# Power.net
KiCad netlist of a schematic drawn in Altium Designer
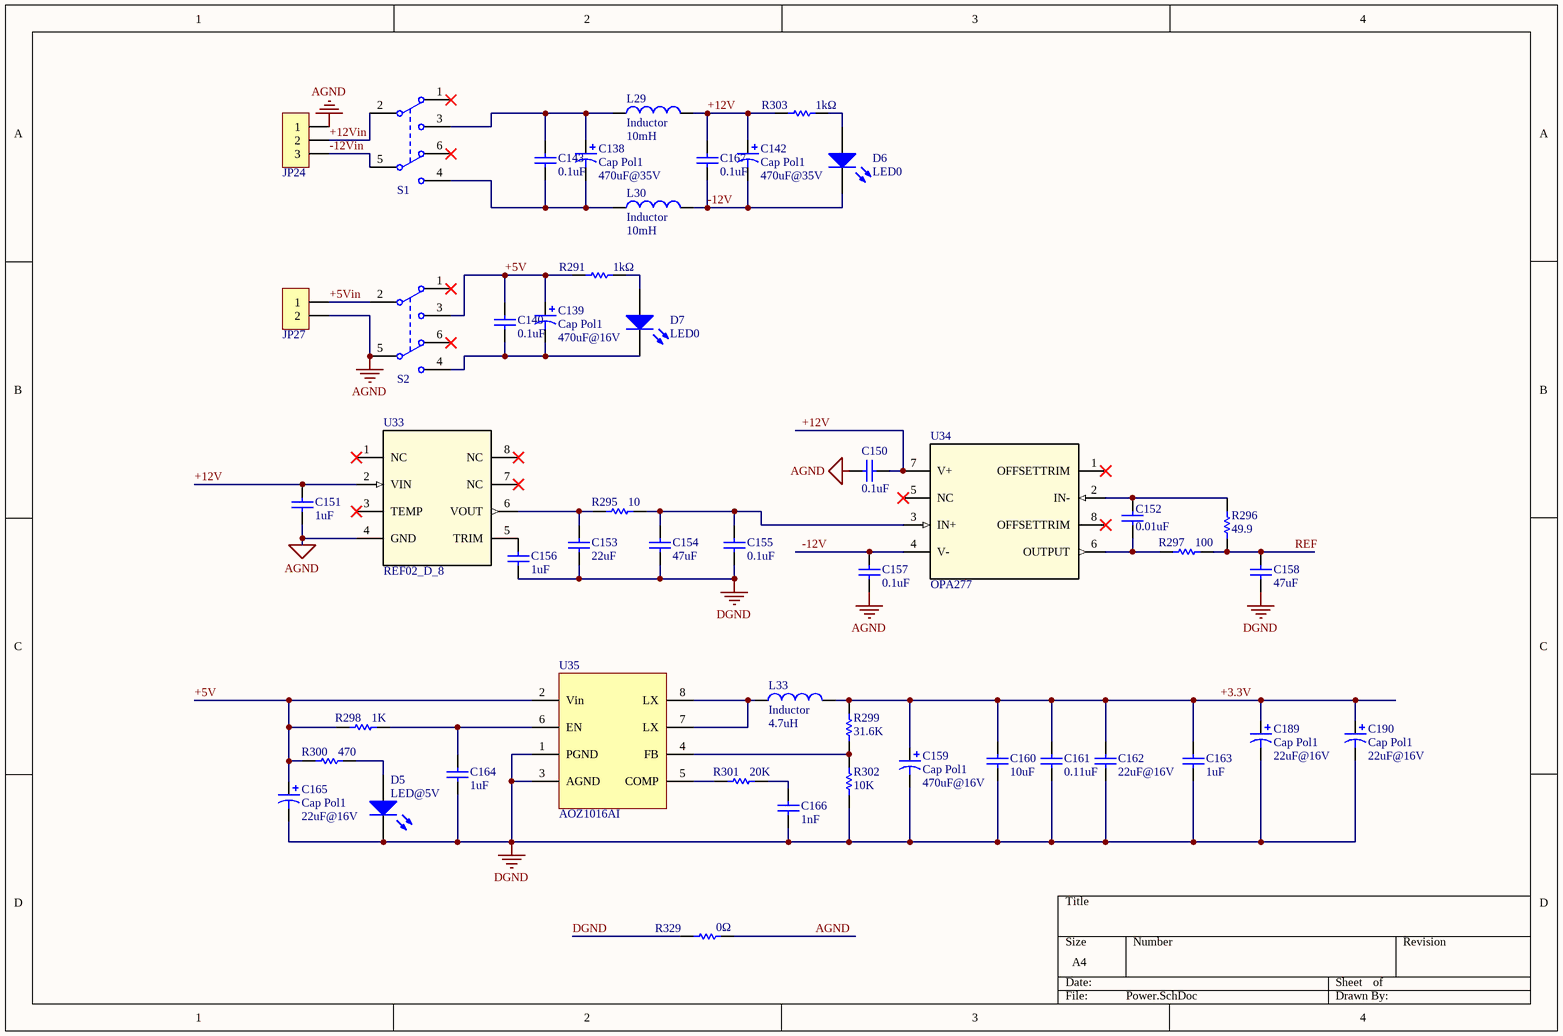
[diagram p0: Power.SchDoc]

(export (version "E")
  (design (tool "Eeschema 10.0.6"))
  (components
    (comp (ref "C138")
      (value "Cap Pol1")
      (footprint "RB7.6-15")
      (description "Polarized Capacitor (Radial)")
      (fields (field (name "ALTIUM_VALUE") "470uF@35V") (field (name "PUBLISHER") "Altium Limited"))
      (libsource (lib "Miscellaneous Devices") (part "Cap Pol1"))
    )
    (comp (ref "C139")
      (value "Cap Pol1")
      (footprint "RB7.6-15")
      (description "Polarized Capacitor (Radial)")
      (fields (field (name "ALTIUM_VALUE") "470uF@16V") (field (name "PUBLISHER") "Altium Limited"))
      (libsource (lib "Miscellaneous Devices") (part "Cap Pol1"))
    )
    (comp (ref "C140")
      (value "0.1uF")
      (footprint "1608[0603]")
      (description "Capacitor")
      (fields (field (name "Comment") "Cap") (field (name "PUBLISHER") "Altium Limited"))
      (libsource (lib "Miscellaneous Devices") (part "Cap"))
    )
    (comp (ref "C142")
      (value "Cap Pol1")
      (footprint "RB7.6-15")
      (description "Polarized Capacitor (Radial)")
      (fields (field (name "ALTIUM_VALUE") "470uF@35V") (field (name "PUBLISHER") "Altium Limited"))
      (libsource (lib "Miscellaneous Devices") (part "Cap Pol1"))
    )
    (comp (ref "C143")
      (value "0.1uF")
      (footprint "1608[0603]")
      (description "Capacitor")
      (fields (field (name "Comment") "Cap") (field (name "PUBLISHER") "Altium Limited"))
      (libsource (lib "Miscellaneous Devices") (part "Cap"))
    )
    (comp (ref "C150")
      (value "0.1uF")
      (footprint "1608[0603]")
      (description "Capacitor")
      (fields (field (name "Comment") "Cap") (field (name "PUBLISHER") "Altium Limited"))
      (libsource (lib "Miscellaneous Devices") (part "Cap"))
    )
    (comp (ref "C151")
      (value "1uF")
      (footprint "1608[0603]")
      (description "Capacitor")
      (fields (field (name "Comment") "Cap") (field (name "PUBLISHER") "Altium Limited"))
      (libsource (lib "Miscellaneous Devices") (part "Cap"))
    )
    (comp (ref "C152")
      (value "0.01uF")
      (footprint "1608[0603]")
      (description "Capacitor")
      (fields (field (name "Comment") "Cap") (field (name "PUBLISHER") "Altium Limited"))
      (libsource (lib "Miscellaneous Devices") (part "Cap"))
    )
    (comp (ref "C153")
      (value "22uF")
      (footprint "C0805")
      (description "Capacitor")
      (fields (field (name "Comment") "Cap") (field (name "PUBLISHER") "Altium Limited"))
      (libsource (lib "Miscellaneous Devices") (part "Cap"))
    )
    (comp (ref "C154")
      (value "47uF")
      (footprint "C1206")
      (description "Capacitor")
      (fields (field (name "Comment") "Cap") (field (name "PUBLISHER") "Altium Limited"))
      (libsource (lib "Miscellaneous Devices") (part "Cap"))
    )
    (comp (ref "C155")
      (value "0.1uF")
      (footprint "1608[0603]")
      (description "Capacitor")
      (fields (field (name "Comment") "Cap") (field (name "PUBLISHER") "Altium Limited"))
      (libsource (lib "Miscellaneous Devices") (part "Cap"))
    )
    (comp (ref "C156")
      (value "1uF")
      (footprint "1608[0603]")
      (description "Capacitor")
      (fields (field (name "Comment") "Cap") (field (name "PUBLISHER") "Altium Limited"))
      (libsource (lib "Miscellaneous Devices") (part "Cap"))
    )
    (comp (ref "C157")
      (value "0.1uF")
      (footprint "1608[0603]")
      (description "Capacitor")
      (fields (field (name "Comment") "Cap") (field (name "PUBLISHER") "Altium Limited"))
      (libsource (lib "Miscellaneous Devices") (part "Cap"))
    )
    (comp (ref "C158")
      (value "47uF")
      (footprint "C1206")
      (description "Capacitor")
      (fields (field (name "Comment") "Cap") (field (name "PUBLISHER") "Altium Limited"))
      (libsource (lib "Miscellaneous Devices") (part "Cap"))
    )
    (comp (ref "C159")
      (value "Cap Pol1")
      (footprint "RB7.6-15")
      (description "Polarized Capacitor (Radial)")
      (fields (field (name "ALTIUM_VALUE") "470uF@16V") (field (name "PUBLISHER") "Altium Limited"))
      (libsource (lib "Miscellaneous Devices") (part "Cap Pol1"))
    )
    (comp (ref "C160")
      (value "10uF")
      (footprint "1608[0603]")
      (description "Capacitor")
      (fields (field (name "Comment") "Cap") (field (name "PUBLISHER") "Altium Limited"))
      (libsource (lib "Miscellaneous Devices") (part "Cap"))
    )
    (comp (ref "C161")
      (value "0.11uF")
      (footprint "1608[0603]")
      (description "Capacitor")
      (fields (field (name "Comment") "Cap") (field (name "PUBLISHER") "Altium Limited"))
      (libsource (lib "Miscellaneous Devices") (part "Cap"))
    )
    (comp (ref "C162")
      (value "22uF@16V")
      (footprint "C0805")
      (description "Capacitor")
      (fields (field (name "Comment") "Cap") (field (name "PUBLISHER") "Altium Limited"))
      (libsource (lib "Miscellaneous Devices") (part "Cap"))
    )
    (comp (ref "C163")
      (value "1uF")
      (footprint "1608[0603]")
      (description "Capacitor")
      (fields (field (name "Comment") "Cap") (field (name "PUBLISHER") "Altium Limited"))
      (libsource (lib "Miscellaneous Devices") (part "Cap"))
    )
    (comp (ref "C164")
      (value "1uF")
      (footprint "1608[0603]")
      (description "Capacitor")
      (fields (field (name "Comment") "Cap") (field (name "PUBLISHER") "Altium Limited"))
      (libsource (lib "Miscellaneous Devices") (part "Cap"))
    )
    (comp (ref "C165")
      (value "Cap Pol1")
      (footprint "RB5-10.5")
      (description "Polarized Capacitor (Radial)")
      (fields (field (name "ALTIUM_VALUE") "22uF@16V") (field (name "PUBLISHER") "Altium Limited"))
      (libsource (lib "Miscellaneous Devices") (part "Cap Pol1"))
    )
    (comp (ref "C166")
      (value "1nF")
      (footprint "1608[0603]")
      (description "Capacitor")
      (fields (field (name "Comment") "Cap") (field (name "PUBLISHER") "Altium Limited"))
      (libsource (lib "Miscellaneous Devices") (part "Cap"))
    )
    (comp (ref "C167")
      (value "0.1uF")
      (footprint "1608[0603]")
      (description "Capacitor")
      (fields (field (name "Comment") "Cap") (field (name "PUBLISHER") "Altium Limited"))
      (libsource (lib "Miscellaneous Devices") (part "Cap"))
    )
    (comp (ref "C189")
      (value "Cap Pol1")
      (footprint "RB5-10.5")
      (description "Polarized Capacitor (Radial)")
      (fields (field (name "ALTIUM_VALUE") "22uF@16V") (field (name "PUBLISHER") "Altium Limited"))
      (libsource (lib "Miscellaneous Devices") (part "Cap Pol1"))
    )
    (comp (ref "C190")
      (value "Cap Pol1")
      (footprint "RB5-10.5")
      (description "Polarized Capacitor (Radial)")
      (fields (field (name "ALTIUM_VALUE") "22uF@16V") (field (name "PUBLISHER") "Altium Limited"))
      (libsource (lib "Miscellaneous Devices") (part "Cap Pol1"))
    )
    (comp (ref "D5")
      (value "LED@5V")
      (footprint "LED-1")
      (description "Typical BLUE SiC LED")
      (fields (field (name "PUBLISHER") "Altium Limited"))
      (libsource (lib "Miscellaneous Devices") (part "LED3"))
    )
    (comp (ref "D6")
      (value "LED0")
      (footprint "LED-0")
      (description "Typical INFRARED GaAs LED")
      (fields (field (name "PUBLISHER") "Altium Limited"))
      (libsource (lib "Miscellaneous Devices") (part "LED0"))
    )
    (comp (ref "D7")
      (value "LED0")
      (footprint "LED-0")
      (description "Typical INFRARED GaAs LED")
      (fields (field (name "PUBLISHER") "Altium Limited"))
      (libsource (lib "Miscellaneous Devices") (part "LED0"))
    )
    (comp (ref "JP24")
      (value "HDR-1X3")
      (footprint "KF128-3.81-3P")
      (description "3P接插件")
      (fields (field (name "版权归属") "源创客"))
      (libsource (lib "4.7   - 接插件-脚距3.81") (part "Header 3"))
    )
    (comp (ref "JP27")
      (value "HDR-1X2")
      (footprint "KF128-3.81-2P")
      (description "2P接插件")
      (fields (field (name "版权归属") "源创客"))
      (libsource (lib "4.7   - 接插件-脚距3.81") (part "Header 2"))
    )
    (comp (ref "L29")
      (value "Inductor")
      (footprint "0402-A")
      (fields (field (name "ALTIUM_VALUE") "10mH") (field (name "PUBLISHER") "Altium Limited"))
      (libsource (lib "Miscellaneous Devices") (part "Inductor"))
    )
    (comp (ref "L30")
      (value "Inductor")
      (footprint "0402-A")
      (fields (field (name "ALTIUM_VALUE") "10mH") (field (name "PUBLISHER") "Altium Limited"))
      (libsource (lib "Miscellaneous Devices") (part "Inductor"))
    )
    (comp (ref "L33")
      (value "Inductor")
      (footprint "2029")
      (fields (field (name "ALTIUM_VALUE") "4.7uH") (field (name "PUBLISHER") "Altium Limited"))
      (libsource (lib "Miscellaneous Devices") (part "Inductor"))
    )
    (comp (ref "R291")
      (value "1kΩ")
      (footprint "14-1210")
      (description "Resistor")
      (fields (field (name "Comment") "Res1") (field (name "PUBLISHER") "Altium Limited"))
      (libsource (lib "Miscellaneous Devices") (part "Res1"))
    )
    (comp (ref "R295")
      (value "10")
      (footprint "1608[0603]")
      (description "Resistor")
      (fields (field (name "Comment") "Res1") (field (name "PUBLISHER") "Altium Limited"))
      (libsource (lib "Miscellaneous Devices") (part "Res1"))
    )
    (comp (ref "R296")
      (value "49.9")
      (footprint "1608[0603]")
      (description "Resistor")
      (fields (field (name "Comment") "Res1") (field (name "PUBLISHER") "Altium Limited"))
      (libsource (lib "Miscellaneous Devices") (part "Res1"))
    )
    (comp (ref "R297")
      (value "100")
      (footprint "1608[0603]")
      (description "Resistor")
      (fields (field (name "Comment") "Res1") (field (name "PUBLISHER") "Altium Limited"))
      (libsource (lib "Miscellaneous Devices") (part "Res1"))
    )
    (comp (ref "R298")
      (value "1K")
      (footprint "1608[0603]")
      (description "Resistor")
      (fields (field (name "Comment") "Res1") (field (name "PUBLISHER") "Altium Limited"))
      (libsource (lib "Miscellaneous Devices") (part "Res1"))
    )
    (comp (ref "R299")
      (value "31.6K")
      (footprint "1608[0603]")
      (description "Resistor")
      (fields (field (name "Comment") "Res1") (field (name "PUBLISHER") "Altium Limited"))
      (libsource (lib "Miscellaneous Devices") (part "Res1"))
    )
    (comp (ref "R300")
      (value "470")
      (footprint "1608[0603]")
      (description "Resistor")
      (fields (field (name "Comment") "Res1") (field (name "PUBLISHER") "Altium Limited"))
      (libsource (lib "Miscellaneous Devices") (part "Res1"))
    )
    (comp (ref "R301")
      (value "20K")
      (footprint "1608[0603]")
      (description "Resistor")
      (fields (field (name "Comment") "Res1") (field (name "PUBLISHER") "Altium Limited"))
      (libsource (lib "Miscellaneous Devices") (part "Res1"))
    )
    (comp (ref "R302")
      (value "10K")
      (footprint "1608[0603]")
      (description "Resistor")
      (fields (field (name "Comment") "Res1") (field (name "PUBLISHER") "Altium Limited"))
      (libsource (lib "Miscellaneous Devices") (part "Res1"))
    )
    (comp (ref "R303")
      (value "1kΩ")
      (footprint "14-1210")
      (description "Resistor")
      (fields (field (name "Comment") "Res1") (field (name "PUBLISHER") "Altium Limited"))
      (libsource (lib "Miscellaneous Devices") (part "Res1"))
    )
    (comp (ref "R329")
      (value "0Ω")
      (footprint "C2512")
      (description "Resistor")
      (fields (field (name "Comment") "Res1") (field (name "PUBLISHER") "Altium Limited"))
      (libsource (lib "Miscellaneous Devices") (part "Res1"))
    )
    (comp (ref "S1")
      (value "SK-22D02")
      (footprint "SK-22D02")
      (description "2路波动开关")
      (fields (field (name "版权归属") "源创客"))
      (libsource (lib "5.1   - 按键-开关") (part "SSW-2P"))
    )
    (comp (ref "S2")
      (value "SK-22D02")
      (footprint "SK-22D02")
      (description "2路波动开关")
      (fields (field (name "版权归属") "源创客"))
      (libsource (lib "5.1   - 按键-开关") (part "SSW-2P"))
    )
    (comp (ref "U33")
      (value "REF02_D_8")
      (footprint "REF02_D_8")
      (fields
        (field (name "MANUFACTURER") "Texas Instruments")
        (field (name "GENERIC_PART_NUMBER") "REF02")
        (field (name "MANUFACTURER_PART_NUMBER") "ref02_d_8")
      )
      (libsource (lib "DSP_FPGA_Lib") (part "REF02_D_8"))
    )
    (comp (ref "U34")
      (value "OPA277")
      (footprint "OPA277")
      (fields
        (field (name "MANUFACTURER") "Texas Instruments")
        (field (name "MANUFACTURER_PART_NUMBER") "opa277_d_8")
      )
      (libsource (lib "DSP_FPGA_Lib") (part "OPA277"))
    )
    (comp (ref "U35")
      (value "AOZ1016AI")
      (footprint "AOZ1016AI")
      (libsource (lib "DSP_FPGA_Lib") (part "AOZ1016AI"))
    )
  )
  (nets
    (net (code "1") (name "/+3.3V") (class "Default")
      (node (ref "C159") (pin "1") (pinfunction "1_1") (pintype "passive"))
      (node (ref "C160") (pin "2") (pinfunction "2_2") (pintype "passive"))
      (node (ref "C161") (pin "2") (pinfunction "2_2") (pintype "passive"))
      (node (ref "C162") (pin "2") (pinfunction "2_2") (pintype "passive"))
      (node (ref "C163") (pin "2") (pinfunction "2_2") (pintype "passive"))
      (node (ref "C189") (pin "1") (pinfunction "1_1") (pintype "passive"))
      (node (ref "C190") (pin "1") (pinfunction "1_1") (pintype "passive"))
      (node (ref "L33") (pin "2") (pinfunction "2_2") (pintype "passive"))
      (node (ref "R299") (pin "1") (pinfunction "1_1") (pintype "passive"))
    )
    (net (code "2") (name "/+5V") (class "Default")
      (node (ref "C139") (pin "1") (pinfunction "1_1") (pintype "passive"))
      (node (ref "C140") (pin "2") (pinfunction "2_2") (pintype "passive"))
      (node (ref "C165") (pin "1") (pinfunction "1_1") (pintype "passive"))
      (node (ref "R291") (pin "1") (pinfunction "1_1") (pintype "passive"))
      (node (ref "R298") (pin "2") (pinfunction "2_2") (pintype "passive"))
      (node (ref "R300") (pin "2") (pinfunction "2_2") (pintype "passive"))
      (node (ref "S2") (pin "3") (pinfunction "3_3") (pintype "passive"))
      (node (ref "U35") (pin "2") (pinfunction "Vin_2") (pintype "passive"))
    )
    (net (code "3") (name "/+5Vin") (class "Default")
      (node (ref "JP27") (pin "1") (pinfunction "1_1") (pintype "passive"))
      (node (ref "S2") (pin "2") (pinfunction "2_2") (pintype "passive"))
    )
    (net (code "4") (name "/+12V") (class "Default")
      (node (ref "C142") (pin "1") (pinfunction "1_1") (pintype "passive"))
      (node (ref "C150") (pin "2") (pinfunction "2_2") (pintype "passive"))
      (node (ref "C151") (pin "2") (pinfunction "2_2") (pintype "passive"))
      (node (ref "C167") (pin "2") (pinfunction "2_2") (pintype "passive"))
      (node (ref "L29") (pin "2") (pinfunction "2_2") (pintype "passive"))
      (node (ref "R303") (pin "1") (pinfunction "1_1") (pintype "passive"))
      (node (ref "U33") (pin "2") (pinfunction "VIN_2") (pintype "input"))
      (node (ref "U34") (pin "7") (pinfunction "V+_7") (pintype "power_in"))
    )
    (net (code "5") (name "/+12Vin") (class "Default")
      (node (ref "JP24") (pin "2") (pinfunction "2_2") (pintype "passive"))
      (node (ref "S1") (pin "2") (pinfunction "2_2") (pintype "passive"))
    )
    (net (code "6") (name "/-12V") (class "Default")
      (node (ref "C142") (pin "2") (pinfunction "2_2") (pintype "passive"))
      (node (ref "C157") (pin "2") (pinfunction "2_2") (pintype "passive"))
      (node (ref "C167") (pin "1") (pinfunction "1_1") (pintype "passive"))
      (node (ref "D6") (pin "2") (pinfunction "K_2") (pintype "passive"))
      (node (ref "L30") (pin "2") (pinfunction "2_2") (pintype "passive"))
      (node (ref "U34") (pin "4") (pinfunction "V-_4") (pintype "power_in"))
    )
    (net (code "7") (name "/-12Vin") (class "Default")
      (node (ref "JP24") (pin "3") (pinfunction "3_3") (pintype "passive"))
      (node (ref "S1") (pin "5") (pinfunction "5_5") (pintype "passive"))
    )
    (net (code "8") (name "/REF") (class "Default")
      (node (ref "C158") (pin "2") (pinfunction "2_2") (pintype "passive"))
      (node (ref "R296") (pin "1") (pinfunction "1_1") (pintype "passive"))
      (node (ref "R297") (pin "1") (pinfunction "1_1") (pintype "passive"))
    )
    (net (code "9") (name "AGND") (class "Default")
      (node (ref "C150") (pin "1") (pinfunction "1_1") (pintype "passive"))
      (node (ref "C151") (pin "1") (pinfunction "1_1") (pintype "passive"))
      (node (ref "C157") (pin "1") (pinfunction "1_1") (pintype "passive"))
      (node (ref "JP24") (pin "1") (pinfunction "1_1") (pintype "passive"))
      (node (ref "JP27") (pin "2") (pinfunction "2_2") (pintype "passive"))
      (node (ref "R329") (pin "1") (pinfunction "1_1") (pintype "passive"))
      (node (ref "S2") (pin "5") (pinfunction "5_5") (pintype "passive"))
      (node (ref "U33") (pin "4") (pinfunction "GND_4") (pintype "power_in"))
    )
    (net (code "10") (name "DGND") (class "Default")
      (node (ref "C153") (pin "1") (pinfunction "1_1") (pintype "passive"))
      (node (ref "C154") (pin "1") (pinfunction "1_1") (pintype "passive"))
      (node (ref "C155") (pin "1") (pinfunction "1_1") (pintype "passive"))
      (node (ref "C156") (pin "1") (pinfunction "1_1") (pintype "passive"))
      (node (ref "C158") (pin "1") (pinfunction "1_1") (pintype "passive"))
      (node (ref "C159") (pin "2") (pinfunction "2_2") (pintype "passive"))
      (node (ref "C160") (pin "1") (pinfunction "1_1") (pintype "passive"))
      (node (ref "C161") (pin "1") (pinfunction "1_1") (pintype "passive"))
      (node (ref "C162") (pin "1") (pinfunction "1_1") (pintype "passive"))
      (node (ref "C163") (pin "1") (pinfunction "1_1") (pintype "passive"))
      (node (ref "C164") (pin "1") (pinfunction "1_1") (pintype "passive"))
      (node (ref "C165") (pin "2") (pinfunction "2_2") (pintype "passive"))
      (node (ref "C166") (pin "1") (pinfunction "1_1") (pintype "passive"))
      (node (ref "C189") (pin "2") (pinfunction "2_2") (pintype "passive"))
      (node (ref "C190") (pin "2") (pinfunction "2_2") (pintype "passive"))
      (node (ref "D5") (pin "2") (pinfunction "K_2") (pintype "passive"))
      (node (ref "R302") (pin "2") (pinfunction "2_2") (pintype "passive"))
      (node (ref "R329") (pin "2") (pinfunction "2_2") (pintype "passive"))
      (node (ref "U35") (pin "1") (pinfunction "PGND_1") (pintype "passive"))
      (node (ref "U35") (pin "3") (pinfunction "AGND_3") (pintype "passive"))
    )
    (net (code "11") (name "Net-(C138-Pad1)") (class "Default")
      (node (ref "C138") (pin "1") (pinfunction "1_1") (pintype "passive"))
      (node (ref "C143") (pin "2") (pinfunction "2_2") (pintype "passive"))
      (node (ref "L29") (pin "1") (pinfunction "1_1") (pintype "passive"))
      (node (ref "S1") (pin "3") (pinfunction "3_3") (pintype "passive"))
    )
    (net (code "12") (name "Net-(C138-Pad2)") (class "Default")
      (node (ref "C138") (pin "2") (pinfunction "2_2") (pintype "passive"))
      (node (ref "C143") (pin "1") (pinfunction "1_1") (pintype "passive"))
      (node (ref "L30") (pin "1") (pinfunction "1_1") (pintype "passive"))
      (node (ref "S1") (pin "4") (pinfunction "4_4") (pintype "passive"))
    )
    (net (code "13") (name "Net-(C166-Pad2)") (class "Default")
      (node (ref "C166") (pin "2") (pinfunction "2_2") (pintype "passive"))
      (node (ref "R301") (pin "1") (pinfunction "1_1") (pintype "passive"))
    )
    (net (code "14") (name "Net-(D5-A)") (class "Default")
      (node (ref "D5") (pin "1") (pinfunction "A_1") (pintype "passive"))
      (node (ref "R300") (pin "1") (pinfunction "1_1") (pintype "passive"))
    )
    (net (code "15") (name "Net-(D6-A)") (class "Default")
      (node (ref "D6") (pin "1") (pinfunction "A_1") (pintype "passive"))
      (node (ref "R303") (pin "2") (pinfunction "2_2") (pintype "passive"))
    )
    (net (code "16") (name "Net-(D7-A)") (class "Default")
      (node (ref "D7") (pin "1") (pinfunction "A_1") (pintype "passive"))
      (node (ref "R291") (pin "2") (pinfunction "2_2") (pintype "passive"))
    )
    (net (code "17") (name "Net-(D7-K)") (class "Default")
      (node (ref "C139") (pin "2") (pinfunction "2_2") (pintype "passive"))
      (node (ref "C140") (pin "1") (pinfunction "1_1") (pintype "passive"))
      (node (ref "D7") (pin "2") (pinfunction "K_2") (pintype "passive"))
      (node (ref "S2") (pin "4") (pinfunction "4_4") (pintype "passive"))
    )
    (net (code "18") (name "Net-(L33-Pad1)") (class "Default")
      (node (ref "L33") (pin "1") (pinfunction "1_1") (pintype "passive"))
      (node (ref "U35") (pin "7") (pinfunction "LX_7") (pintype "passive"))
      (node (ref "U35") (pin "8") (pinfunction "LX_8") (pintype "passive"))
    )
    (net (code "19") (name "Net-(U33-TRIM)") (class "Default")
      (node (ref "C156") (pin "2") (pinfunction "2_2") (pintype "passive"))
      (node (ref "U33") (pin "5") (pinfunction "TRIM_5") (pintype "passive"))
    )
    (net (code "20") (name "Net-(U33-VOUT)") (class "Default")
      (node (ref "C153") (pin "2") (pinfunction "2_2") (pintype "passive"))
      (node (ref "R295") (pin "2") (pinfunction "2_2") (pintype "passive"))
      (node (ref "U33") (pin "6") (pinfunction "VOUT_6") (pintype "output"))
    )
    (net (code "21") (name "Net-(U34-IN+)") (class "Default")
      (node (ref "C154") (pin "2") (pinfunction "2_2") (pintype "passive"))
      (node (ref "C155") (pin "2") (pinfunction "2_2") (pintype "passive"))
      (node (ref "R295") (pin "1") (pinfunction "1_1") (pintype "passive"))
      (node (ref "U34") (pin "3") (pinfunction "IN+_3") (pintype "input"))
    )
    (net (code "22") (name "Net-(U34-IN-)") (class "Default")
      (node (ref "C152") (pin "2") (pinfunction "2_2") (pintype "passive"))
      (node (ref "R296") (pin "2") (pinfunction "2_2") (pintype "passive"))
      (node (ref "U34") (pin "2") (pinfunction "IN-_2") (pintype "input"))
    )
    (net (code "23") (name "Net-(U34-OUTPUT)") (class "Default")
      (node (ref "C152") (pin "1") (pinfunction "1_1") (pintype "passive"))
      (node (ref "R297") (pin "2") (pinfunction "2_2") (pintype "passive"))
      (node (ref "U34") (pin "6") (pinfunction "OUTPUT_6") (pintype "output"))
    )
    (net (code "24") (name "Net-(U35-COMP)") (class "Default")
      (node (ref "R301") (pin "2") (pinfunction "2_2") (pintype "passive"))
      (node (ref "U35") (pin "5") (pinfunction "COMP_5") (pintype "passive"))
    )
    (net (code "25") (name "Net-(U35-EN)") (class "Default")
      (node (ref "C164") (pin "2") (pinfunction "2_2") (pintype "passive"))
      (node (ref "R298") (pin "1") (pinfunction "1_1") (pintype "passive"))
      (node (ref "U35") (pin "6") (pinfunction "EN_6") (pintype "passive"))
    )
    (net (code "26") (name "Net-(U35-FB)") (class "Default")
      (node (ref "R299") (pin "2") (pinfunction "2_2") (pintype "passive"))
      (node (ref "R302") (pin "1") (pinfunction "1_1") (pintype "passive"))
      (node (ref "U35") (pin "4") (pinfunction "FB_4") (pintype "passive"))
    )
    (net (code "27") (name "unconnected-(S1-Pad1)") (class "Default")
      (node (ref "S1") (pin "1") (pinfunction "1_1") (pintype "passive+no_connect"))
    )
    (net (code "28") (name "unconnected-(S1-Pad6)") (class "Default")
      (node (ref "S1") (pin "6") (pinfunction "6_6") (pintype "passive+no_connect"))
    )
    (net (code "29") (name "unconnected-(S2-Pad1)") (class "Default")
      (node (ref "S2") (pin "1") (pinfunction "1_1") (pintype "passive+no_connect"))
    )
    (net (code "30") (name "unconnected-(S2-Pad6)") (class "Default")
      (node (ref "S2") (pin "6") (pinfunction "6_6") (pintype "passive+no_connect"))
    )
    (net (code "31") (name "unconnected-(U33-NC-Pad1)") (class "Default")
      (node (ref "U33") (pin "1") (pinfunction "NC_1") (pintype "passive+no_connect"))
    )
    (net (code "32") (name "unconnected-(U33-NC-Pad7)") (class "Default")
      (node (ref "U33") (pin "7") (pinfunction "NC_7") (pintype "passive+no_connect"))
    )
    (net (code "33") (name "unconnected-(U33-NC-Pad8)") (class "Default")
      (node (ref "U33") (pin "8") (pinfunction "NC_8") (pintype "passive+no_connect"))
    )
    (net (code "34") (name "unconnected-(U33-TEMP-Pad3)") (class "Default")
      (node (ref "U33") (pin "3") (pinfunction "TEMP_3") (pintype "passive+no_connect"))
    )
    (net (code "35") (name "unconnected-(U34-NC-Pad5)") (class "Default")
      (node (ref "U34") (pin "5") (pinfunction "NC_5") (pintype "passive+no_connect"))
    )
    (net (code "36") (name "unconnected-(U34-OFFSETTRIM-Pad1)") (class "Default")
      (node (ref "U34") (pin "1") (pinfunction "OFFSETTRIM_1") (pintype "passive+no_connect"))
    )
    (net (code "37") (name "unconnected-(U34-OFFSETTRIM-Pad8)") (class "Default")
      (node (ref "U34") (pin "8") (pinfunction "OFFSETTRIM_8") (pintype "passive+no_connect"))
    )
  )
)
